# ir_remote.net
KiCad netlist of a schematic drawn in EAGLE
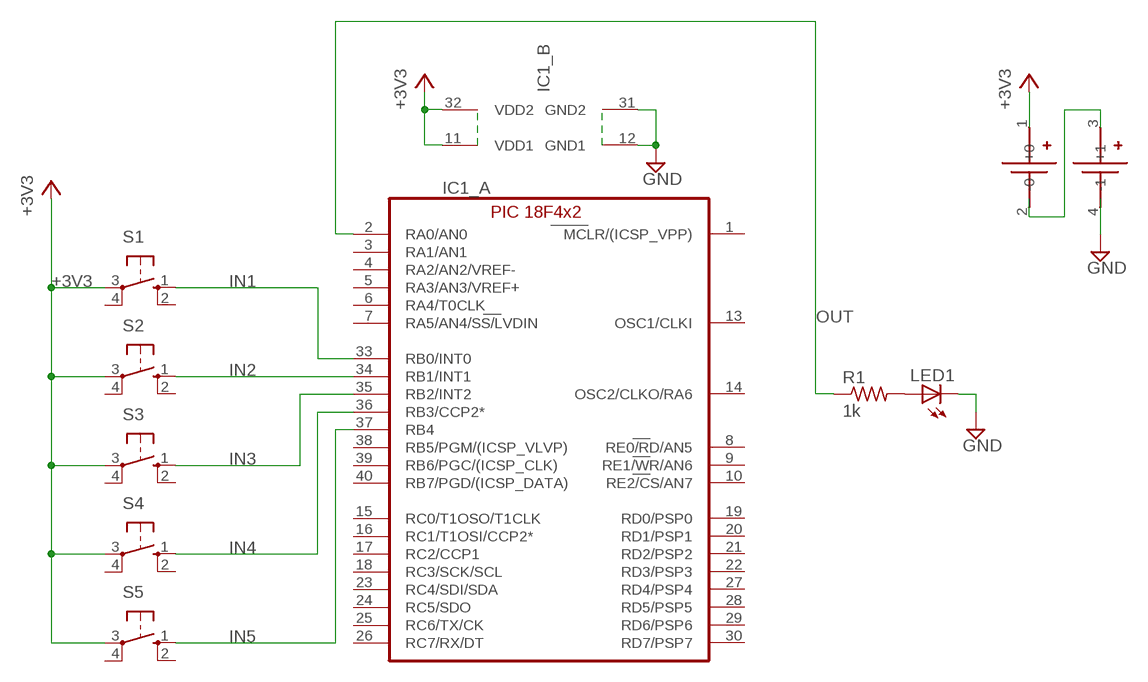
[diagram p0: schematic, sheet 1]

(export (version "E")
  (design (tool "Eeschema 10.0.6"))
  (components
    (comp (ref "IC1")
      (value "PIC18F4X2DIL40")
      (footprint "eagle-import:DIL40")
      (libsource (lib "eagle-import") (part "PIC18F4X2DIL40"))
    )
    (comp (ref "LED1")
      (value "LED5MM")
      (footprint "eagle-import:LED5MM")
      (libsource (lib "eagle-import") (part "LED5MM"))
    )
    (comp (ref "R1")
      (value "1k")
      (footprint "eagle-import:0207_12")
      (libsource (lib "eagle-import") (part "R-US_0207/12"))
    )
    (comp (ref "S1")
      (value "10-XX")
      (footprint "eagle-import:B3F-10XX")
      (fields (field (name "MPN") "B3F-1000"))
      (libsource (lib "eagle-import") (part "10-XX"))
    )
    (comp (ref "S2")
      (value "10-XX")
      (footprint "eagle-import:B3F-10XX")
      (fields (field (name "MPN") "B3F-1000"))
      (libsource (lib "eagle-import") (part "10-XX"))
    )
    (comp (ref "S3")
      (value "10-XX")
      (footprint "eagle-import:B3F-10XX")
      (fields (field (name "MPN") "B3F-1000"))
      (libsource (lib "eagle-import") (part "10-XX"))
    )
    (comp (ref "S4")
      (value "10-XX")
      (footprint "eagle-import:B3F-10XX")
      (fields (field (name "MPN") "B3F-1000"))
      (libsource (lib "eagle-import") (part "10-XX"))
    )
    (comp (ref "S5")
      (value "10-XX")
      (footprint "eagle-import:B3F-10XX")
      (fields (field (name "MPN") "B3F-1000"))
      (libsource (lib "eagle-import") (part "10-XX"))
    )
    (comp (ref "U$1")
      (value "BLOSSOM-BLM-18650-2PCS")
      (footprint "eagle-import:BLOSSOM-BLM-18650-2PCS")
      (libsource (lib "eagle-import") (part "BLOSSOM-BLM-18650-2PCS"))
    )
  )
  (nets
    (net (code "1") (name "+3V3") (class "Default")
      (node (ref "IC1") (pin "11") (pinfunction "VDD1_11") (pintype "power_in"))
      (node (ref "IC1") (pin "32") (pinfunction "VDD2_32") (pintype "power_in"))
      (node (ref "S1") (pin "3") (pinfunction "P_3") (pintype "passive"))
      (node (ref "S2") (pin "3") (pinfunction "P_3") (pintype "passive"))
      (node (ref "S3") (pin "3") (pinfunction "P_3") (pintype "passive"))
      (node (ref "S4") (pin "3") (pinfunction "P_3") (pintype "passive"))
      (node (ref "S5") (pin "3") (pinfunction "P_3") (pintype "passive"))
      (node (ref "U$1") (pin "1") (pinfunction "+0_1") (pintype "bidirectional"))
    )
    (net (code "2") (name "/IN1") (class "Default")
      (node (ref "IC1") (pin "33") (pinfunction "RB0/INT0_33") (pintype "bidirectional"))
      (node (ref "S1") (pin "1") (pinfunction "S_1") (pintype "passive"))
    )
    (net (code "3") (name "/IN2") (class "Default")
      (node (ref "IC1") (pin "34") (pinfunction "RB1/INT1_34") (pintype "bidirectional"))
      (node (ref "S2") (pin "1") (pinfunction "S_1") (pintype "passive"))
    )
    (net (code "4") (name "/IN3") (class "Default")
      (node (ref "IC1") (pin "35") (pinfunction "RB2/INT2_35") (pintype "bidirectional"))
      (node (ref "S3") (pin "1") (pinfunction "S_1") (pintype "passive"))
    )
    (net (code "5") (name "/IN4") (class "Default")
      (node (ref "IC1") (pin "36") (pinfunction "RB3/CCP2*_36") (pintype "bidirectional"))
      (node (ref "S4") (pin "1") (pinfunction "S_1") (pintype "passive"))
    )
    (net (code "6") (name "/IN5") (class "Default")
      (node (ref "IC1") (pin "37") (pinfunction "RB4_37") (pintype "bidirectional"))
      (node (ref "S5") (pin "1") (pinfunction "S_1") (pintype "passive"))
    )
    (net (code "7") (name "/MCLR{slash}(ICSP_VPP)") (class "Default")
      (node (ref "IC1") (pin "1") (pinfunction "MCLR/(ICSP_VPP)_1") (pintype "power_in"))
    )
    (net (code "8") (name "/OSC1{slash}CLKI") (class "Default")
      (node (ref "IC1") (pin "13") (pinfunction "OSC1/CLKI_13") (pintype "power_in"))
    )
    (net (code "9") (name "/OSC2{slash}CLKO{slash}RA6") (class "Default")
      (node (ref "IC1") (pin "14") (pinfunction "OSC2/CLKO/RA6_14") (pintype "power_in"))
    )
    (net (code "10") (name "/OUT") (class "Default")
      (node (ref "IC1") (pin "2") (pinfunction "RA0/AN0_2") (pintype "bidirectional"))
      (node (ref "R1") (pin "1") (pinfunction "1_1") (pintype "passive"))
    )
    (net (code "11") (name "GND") (class "Default")
      (node (ref "IC1") (pin "12") (pinfunction "GND1_12") (pintype "power_in"))
      (node (ref "IC1") (pin "31") (pinfunction "GND2_31") (pintype "power_in"))
      (node (ref "LED1") (pin "K") (pinfunction "C_K") (pintype "passive"))
    )
    (net (code "12") (name "Net-(LED1-PadA)") (class "Default")
      (node (ref "LED1") (pin "A") (pinfunction "A_A") (pintype "passive"))
      (node (ref "R1") (pin "2") (pinfunction "2_2") (pintype "passive"))
    )
    (net (code "13") (name "unconnected-(IC1A-RA1{slash}AN1-Pad3)") (class "Default")
      (node (ref "IC1") (pin "3") (pinfunction "RA1/AN1_3") (pintype "bidirectional"))
    )
    (net (code "14") (name "unconnected-(IC1A-RA2{slash}AN2{slash}VREF--Pad4)") (class "Default")
      (node (ref "IC1") (pin "4") (pinfunction "RA2/AN2/VREF-_4") (pintype "bidirectional"))
    )
    (net (code "15") (name "unconnected-(IC1A-RA3{slash}AN3{slash}VREF+-Pad5)") (class "Default")
      (node (ref "IC1") (pin "5") (pinfunction "RA3/AN3/VREF+_5") (pintype "bidirectional"))
    )
    (net (code "16") (name "unconnected-(IC1A-RA4{slash}T0CLK-Pad6)") (class "Default")
      (node (ref "IC1") (pin "6") (pinfunction "RA4/T0CLK_6") (pintype "bidirectional"))
    )
    (net (code "17") (name "unconnected-(IC1A-RA5{slash}AN4{slash}SS{slash}LVDIN-Pad7)") (class "Default")
      (node (ref "IC1") (pin "7") (pinfunction "RA5/AN4/SS/LVDIN_7") (pintype "bidirectional"))
    )
    (net (code "18") (name "unconnected-(IC1A-RB5{slash}PGM{slash}(ICSP_VLVP)-Pad38)") (class "Default")
      (node (ref "IC1") (pin "38") (pinfunction "RB5/PGM/(ICSP_VLVP)_38") (pintype "bidirectional"))
    )
    (net (code "19") (name "unconnected-(IC1A-RB6{slash}PGC{slash}(ICSP_CLK)-Pad39)") (class "Default")
      (node (ref "IC1") (pin "39") (pinfunction "RB6/PGC/(ICSP_CLK)_39") (pintype "bidirectional"))
    )
    (net (code "20") (name "unconnected-(IC1A-RB7{slash}PGD{slash}(ICSP_DATA)-Pad40)") (class "Default")
      (node (ref "IC1") (pin "40") (pinfunction "RB7/PGD/(ICSP_DATA)_40") (pintype "bidirectional"))
    )
    (net (code "21") (name "unconnected-(IC1A-RC0{slash}T1OSO{slash}T1CLK-Pad15)") (class "Default")
      (node (ref "IC1") (pin "15") (pinfunction "RC0/T1OSO/T1CLK_15") (pintype "bidirectional"))
    )
    (net (code "22") (name "unconnected-(IC1A-RC1{slash}T1OSI{slash}CCP2*-Pad16)") (class "Default")
      (node (ref "IC1") (pin "16") (pinfunction "RC1/T1OSI/CCP2*_16") (pintype "bidirectional"))
    )
    (net (code "23") (name "unconnected-(IC1A-RC2{slash}CCP1-Pad17)") (class "Default")
      (node (ref "IC1") (pin "17") (pinfunction "RC2/CCP1_17") (pintype "bidirectional"))
    )
    (net (code "24") (name "unconnected-(IC1A-RC3{slash}SCK{slash}SCL-Pad18)") (class "Default")
      (node (ref "IC1") (pin "18") (pinfunction "RC3/SCK/SCL_18") (pintype "bidirectional"))
    )
    (net (code "25") (name "unconnected-(IC1A-RC4{slash}SDI{slash}SDA-Pad23)") (class "Default")
      (node (ref "IC1") (pin "23") (pinfunction "RC4/SDI/SDA_23") (pintype "bidirectional"))
    )
    (net (code "26") (name "unconnected-(IC1A-RC5{slash}SDO-Pad24)") (class "Default")
      (node (ref "IC1") (pin "24") (pinfunction "RC5/SDO_24") (pintype "bidirectional"))
    )
    (net (code "27") (name "unconnected-(IC1A-RC6{slash}TX{slash}CK-Pad25)") (class "Default")
      (node (ref "IC1") (pin "25") (pinfunction "RC6/TX/CK_25") (pintype "bidirectional"))
    )
    (net (code "28") (name "unconnected-(IC1A-RC7{slash}RX{slash}DT-Pad26)") (class "Default")
      (node (ref "IC1") (pin "26") (pinfunction "RC7/RX/DT_26") (pintype "bidirectional"))
    )
    (net (code "29") (name "unconnected-(IC1A-RD0{slash}PSP0-Pad19)") (class "Default")
      (node (ref "IC1") (pin "19") (pinfunction "RD0/PSP0_19") (pintype "bidirectional"))
    )
    (net (code "30") (name "unconnected-(IC1A-RD1{slash}PSP1-Pad20)") (class "Default")
      (node (ref "IC1") (pin "20") (pinfunction "RD1/PSP1_20") (pintype "bidirectional"))
    )
    (net (code "31") (name "unconnected-(IC1A-RD2{slash}PSP2-Pad21)") (class "Default")
      (node (ref "IC1") (pin "21") (pinfunction "RD2/PSP2_21") (pintype "bidirectional"))
    )
    (net (code "32") (name "unconnected-(IC1A-RD3{slash}PSP3-Pad22)") (class "Default")
      (node (ref "IC1") (pin "22") (pinfunction "RD3/PSP3_22") (pintype "bidirectional"))
    )
    (net (code "33") (name "unconnected-(IC1A-RD4{slash}PSP4-Pad27)") (class "Default")
      (node (ref "IC1") (pin "27") (pinfunction "RD4/PSP4_27") (pintype "bidirectional"))
    )
    (net (code "34") (name "unconnected-(IC1A-RD5{slash}PSP5-Pad28)") (class "Default")
      (node (ref "IC1") (pin "28") (pinfunction "RD5/PSP5_28") (pintype "bidirectional"))
    )
    (net (code "35") (name "unconnected-(IC1A-RD6{slash}PSP6-Pad29)") (class "Default")
      (node (ref "IC1") (pin "29") (pinfunction "RD6/PSP6_29") (pintype "bidirectional"))
    )
    (net (code "36") (name "unconnected-(IC1A-RD7{slash}PSP7-Pad30)") (class "Default")
      (node (ref "IC1") (pin "30") (pinfunction "RD7/PSP7_30") (pintype "bidirectional"))
    )
    (net (code "37") (name "unconnected-(IC1A-RE0{slash}RD{slash}AN5-Pad8)") (class "Default")
      (node (ref "IC1") (pin "8") (pinfunction "RE0/RD/AN5_8") (pintype "bidirectional"))
    )
    (net (code "38") (name "unconnected-(IC1A-RE1{slash}WR{slash}AN6-Pad9)") (class "Default")
      (node (ref "IC1") (pin "9") (pinfunction "RE1/WR/AN6_9") (pintype "bidirectional"))
    )
    (net (code "39") (name "unconnected-(IC1A-RE2{slash}CS{slash}AN7-Pad10)") (class "Default")
      (node (ref "IC1") (pin "10") (pinfunction "RE2/CS/AN7_10") (pintype "bidirectional"))
    )
    (net (code "40") (name "unconnected-(S1-P1-Pad4)") (class "Default")
      (node (ref "S1") (pin "4") (pinfunction "P1_4") (pintype "passive"))
    )
    (net (code "41") (name "unconnected-(S1-S1-Pad2)") (class "Default")
      (node (ref "S1") (pin "2") (pinfunction "S1_2") (pintype "passive"))
    )
    (net (code "42") (name "unconnected-(S2-P1-Pad4)") (class "Default")
      (node (ref "S2") (pin "4") (pinfunction "P1_4") (pintype "passive"))
    )
    (net (code "43") (name "unconnected-(S2-S1-Pad2)") (class "Default")
      (node (ref "S2") (pin "2") (pinfunction "S1_2") (pintype "passive"))
    )
    (net (code "44") (name "unconnected-(S3-P1-Pad4)") (class "Default")
      (node (ref "S3") (pin "4") (pinfunction "P1_4") (pintype "passive"))
    )
    (net (code "45") (name "unconnected-(S3-S1-Pad2)") (class "Default")
      (node (ref "S3") (pin "2") (pinfunction "S1_2") (pintype "passive"))
    )
    (net (code "46") (name "unconnected-(S4-P1-Pad4)") (class "Default")
      (node (ref "S4") (pin "4") (pinfunction "P1_4") (pintype "passive"))
    )
    (net (code "47") (name "unconnected-(S4-S1-Pad2)") (class "Default")
      (node (ref "S4") (pin "2") (pinfunction "S1_2") (pintype "passive"))
    )
    (net (code "48") (name "unconnected-(S5-P1-Pad4)") (class "Default")
      (node (ref "S5") (pin "4") (pinfunction "P1_4") (pintype "passive"))
    )
    (net (code "49") (name "unconnected-(S5-S1-Pad2)") (class "Default")
      (node (ref "S5") (pin "2") (pinfunction "S1_2") (pintype "passive"))
    )
    (net (code "50") (name "unconnected-(U$1-+1-Pad3)") (class "Default")
      (node (ref "U$1") (pin "3") (pinfunction "+1_3") (pintype "bidirectional"))
    )
    (net (code "51") (name "unconnected-(U$1--0-Pad2)") (class "Default")
      (node (ref "U$1") (pin "2") (pinfunction "-0_2") (pintype "bidirectional"))
    )
    (net (code "52") (name "unconnected-(U$1--1-Pad4)") (class "Default")
      (node (ref "U$1") (pin "4") (pinfunction "-1_4") (pintype "bidirectional"))
    )
  )
)
